# insect-robot.net
KiCad netlist of a schematic drawn in EAGLE
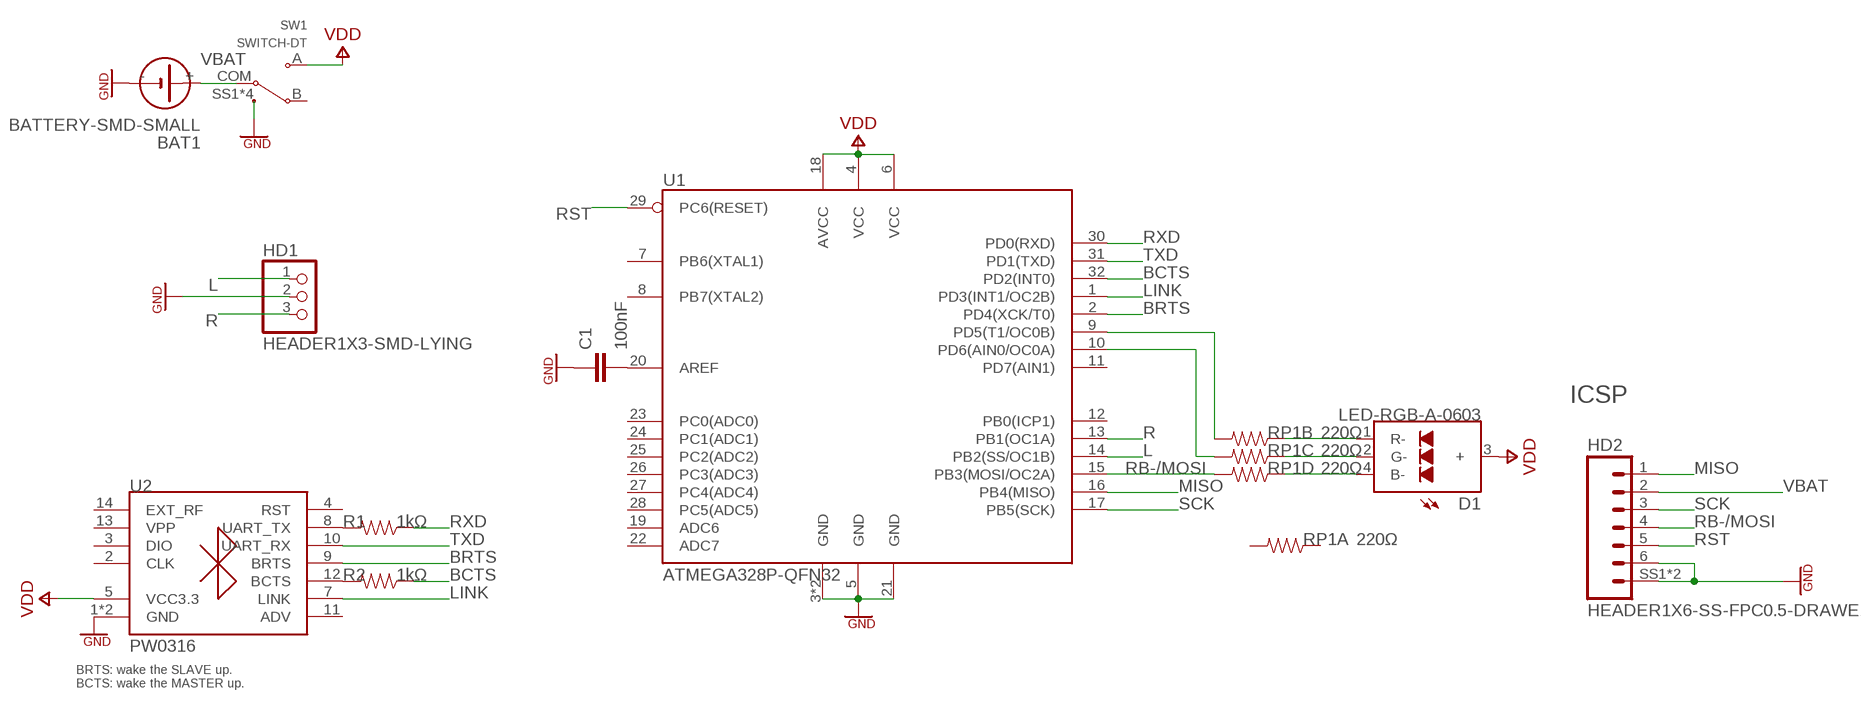
[diagram p0: schematic, sheet 1]

(export (version "E")
  (design (tool "Eeschema 10.0.6"))
  (components
    (comp (ref "BAT1")
      (value "BATTERY-SMD-SMALL")
      (footprint "eagle-import:BAT-SMD-SMALL")
      (libsource (lib "eagle-import") (part "BATTERY-SMD-SMALL"))
    )
    (comp (ref "C1")
      (value "100nF")
      (footprint "eagle-import:SMD0603")
      (libsource (lib "eagle-import") (part "CAP-0603"))
    )
    (comp (ref "D1")
      (value "LED-RGB-A-0603")
      (footprint "eagle-import:LED-0603X2")
      (libsource (lib "eagle-import") (part "LED-RGB-A-0603"))
    )
    (comp (ref "HD1")
      (value "HEADER1X3-SMD-LYING")
      (footprint "eagle-import:SMD-1X3-LYING")
      (libsource (lib "eagle-import") (part "HEADER1X3-SMD-LYING"))
    )
    (comp (ref "HD2")
      (value "HEADER1X6-SS-FPC0.5-DRAWER")
      (footprint "eagle-import:FPC0.5-6-DRAWER")
      (libsource (lib "eagle-import") (part "HEADER1X6-SS-FPC0.5-DRAWER"))
    )
    (comp (ref "R1")
      (value "1kΩ")
      (footprint "eagle-import:SMD0603")
      (libsource (lib "eagle-import") (part "RES-0603"))
    )
    (comp (ref "R2")
      (value "1kΩ")
      (footprint "eagle-import:SMD0603")
      (libsource (lib "eagle-import") (part "RES-0603"))
    )
    (comp (ref "RP1")
      (value "220Ω")
      (footprint "eagle-import:RP0603")
      (libsource (lib "eagle-import") (part "RP-0603"))
    )
    (comp (ref "SW1")
      (value "SWITCH-DT")
      (footprint "eagle-import:SWITCH-SMD-6.7X2.7")
      (libsource (lib "eagle-import") (part "SWITCH-DT"))
    )
    (comp (ref "U1")
      (value "ATMEGA328P-QFN32")
      (footprint "eagle-import:QFN32")
      (libsource (lib "eagle-import") (part "ATMEGA328P-QFN32"))
    )
    (comp (ref "U2")
      (value "PW0316")
      (footprint "eagle-import:PW0316")
      (libsource (lib "eagle-import") (part "PW0316"))
    )
  )
  (nets
    (net (code "1") (name "/BCTS") (class "Default")
      (node (ref "R2") (pin "1") (pinfunction "1_1") (pintype "passive"))
      (node (ref "U1") (pin "32") (pinfunction "PD2(INT0)_32") (pintype "bidirectional"))
    )
    (net (code "2") (name "/BRTS") (class "Default")
      (node (ref "U1") (pin "2") (pinfunction "PD4(XCK/T0)_2") (pintype "bidirectional"))
      (node (ref "U2") (pin "9") (pinfunction "BRTS_9") (pintype "bidirectional"))
    )
    (net (code "3") (name "/L") (class "Default")
      (node (ref "HD1") (pin "1") (pinfunction "1_1") (pintype "passive"))
      (node (ref "U1") (pin "14") (pinfunction "PB2(SS/OC1B)_14") (pintype "bidirectional"))
    )
    (net (code "4") (name "/LINK") (class "Default")
      (node (ref "U1") (pin "1") (pinfunction "PD3(INT1/OC2B)_1") (pintype "bidirectional"))
      (node (ref "U2") (pin "7") (pinfunction "LINK_7") (pintype "bidirectional"))
    )
    (net (code "5") (name "/MISO") (class "Default")
      (node (ref "HD2") (pin "1") (pinfunction "1_1") (pintype "passive"))
      (node (ref "U1") (pin "16") (pinfunction "PB4(MISO)_16") (pintype "bidirectional"))
    )
    (net (code "6") (name "/R") (class "Default")
      (node (ref "HD1") (pin "3") (pinfunction "3_3") (pintype "passive"))
      (node (ref "U1") (pin "13") (pinfunction "PB1(OC1A)_13") (pintype "bidirectional"))
    )
    (net (code "7") (name "/RB-{slash}MOSI") (class "Default")
      (node (ref "HD2") (pin "4") (pinfunction "4_4") (pintype "passive"))
      (node (ref "RP1") (pin "8") (pinfunction "2_8") (pintype "passive"))
      (node (ref "U1") (pin "15") (pinfunction "PB3(MOSI/OC2A)_15") (pintype "bidirectional"))
    )
    (net (code "8") (name "/RST") (class "Default")
      (node (ref "HD2") (pin "5") (pinfunction "5_5") (pintype "passive"))
      (node (ref "U1") (pin "29") (pinfunction "PC6(RESET)_29") (pintype "bidirectional"))
    )
    (net (code "9") (name "/RXD") (class "Default")
      (node (ref "R1") (pin "1") (pinfunction "1_1") (pintype "passive"))
      (node (ref "U1") (pin "30") (pinfunction "PD0(RXD)_30") (pintype "bidirectional"))
    )
    (net (code "10") (name "/SCK") (class "Default")
      (node (ref "HD2") (pin "3") (pinfunction "3_3") (pintype "passive"))
      (node (ref "U1") (pin "17") (pinfunction "PB5(SCK)_17") (pintype "bidirectional"))
    )
    (net (code "11") (name "/TXD") (class "Default")
      (node (ref "U1") (pin "31") (pinfunction "PD1(TXD)_31") (pintype "bidirectional"))
      (node (ref "U2") (pin "10") (pinfunction "UART_RX_10") (pintype "bidirectional"))
    )
    (net (code "12") (name "/VBAT") (class "Default")
      (node (ref "BAT1") (pin "+") (pinfunction "+_+") (pintype "passive"))
      (node (ref "HD2") (pin "2") (pinfunction "2_2") (pintype "passive"))
      (node (ref "SW1") (pin "COM") (pinfunction "COM_COM") (pintype "passive"))
    )
    (net (code "13") (name "GND") (class "Default")
      (node (ref "BAT1") (pin "-") (pinfunction "-_-") (pintype "passive"))
      (node (ref "C1") (pin "1") (pinfunction "1_1") (pintype "passive"))
      (node (ref "HD1") (pin "2") (pinfunction "2_2") (pintype "passive"))
      (node (ref "HD2") (pin "6") (pinfunction "6_6") (pintype "passive"))
      (node (ref "HD2") (pin "SS1") (pinfunction "7_SS1") (pintype "passive"))
      (node (ref "HD2") (pin "SS2") (pinfunction "7_SS2") (pintype "passive"))
      (node (ref "SW1") (pin "SS1") (pinfunction "SS_SS1") (pintype "bidirectional"))
      (node (ref "SW1") (pin "SS2") (pinfunction "SS_SS2") (pintype "bidirectional"))
      (node (ref "SW1") (pin "SS3") (pinfunction "SS_SS3") (pintype "bidirectional"))
      (node (ref "SW1") (pin "SS4") (pinfunction "SS_SS4") (pintype "bidirectional"))
      (node (ref "U1") (pin "21") (pinfunction "GND_21") (pintype "bidirectional"))
      (node (ref "U1") (pin "3") (pinfunction "GND_3") (pintype "bidirectional"))
      (node (ref "U1") (pin "5") (pinfunction "GND_5") (pintype "bidirectional"))
      (node (ref "U1") (pin "EP") (pinfunction "GND_EP") (pintype "bidirectional"))
      (node (ref "U2") (pin "1") (pinfunction "GND_1") (pintype "bidirectional"))
      (node (ref "U2") (pin "6") (pinfunction "GND_6") (pintype "bidirectional"))
    )
    (net (code "14") (name "Net-(D1-B-)") (class "Default")
      (node (ref "D1") (pin "4") (pinfunction "B-_4") (pintype "bidirectional"))
      (node (ref "RP1") (pin "7") (pinfunction "1_7") (pintype "passive"))
    )
    (net (code "15") (name "Net-(D1-G-)") (class "Default")
      (node (ref "D1") (pin "2") (pinfunction "G-_2") (pintype "bidirectional"))
      (node (ref "RP1") (pin "5") (pinfunction "1_5") (pintype "passive"))
    )
    (net (code "16") (name "Net-(D1-R-)") (class "Default")
      (node (ref "D1") (pin "1") (pinfunction "R-_1") (pintype "bidirectional"))
      (node (ref "RP1") (pin "3") (pinfunction "1_3") (pintype "passive"))
    )
    (net (code "17") (name "Net-(RP1B-2)") (class "Default")
      (node (ref "RP1") (pin "4") (pinfunction "2_4") (pintype "passive"))
      (node (ref "U1") (pin "9") (pinfunction "PD5(T1/OC0B)_9") (pintype "bidirectional"))
    )
    (net (code "18") (name "Net-(RP1C-2)") (class "Default")
      (node (ref "RP1") (pin "6") (pinfunction "2_6") (pintype "passive"))
      (node (ref "U1") (pin "10") (pinfunction "PD6(AIN0/OC0A)_10") (pintype "bidirectional"))
    )
    (net (code "19") (name "Net-(U1-AREF)") (class "Default")
      (node (ref "C1") (pin "2") (pinfunction "2_2") (pintype "passive"))
      (node (ref "U1") (pin "20") (pinfunction "AREF_20") (pintype "bidirectional"))
    )
    (net (code "20") (name "Net-(U2-BCTS)") (class "Default")
      (node (ref "R2") (pin "2") (pinfunction "2_2") (pintype "passive"))
      (node (ref "U2") (pin "12") (pinfunction "BCTS_12") (pintype "bidirectional"))
    )
    (net (code "21") (name "Net-(U2-UART_TX)") (class "Default")
      (node (ref "R1") (pin "2") (pinfunction "2_2") (pintype "passive"))
      (node (ref "U2") (pin "8") (pinfunction "UART_TX_8") (pintype "bidirectional"))
    )
    (net (code "22") (name "VDD") (class "Default")
      (node (ref "D1") (pin "3") (pinfunction "+_3") (pintype "bidirectional"))
      (node (ref "SW1") (pin "A") (pinfunction "A_A") (pintype "passive"))
      (node (ref "U1") (pin "18") (pinfunction "AVCC_18") (pintype "bidirectional"))
      (node (ref "U1") (pin "4") (pinfunction "VCC_4") (pintype "bidirectional"))
      (node (ref "U1") (pin "6") (pinfunction "VCC_6") (pintype "bidirectional"))
      (node (ref "U2") (pin "5") (pinfunction "VCC3.3_5") (pintype "bidirectional"))
    )
    (net (code "23") (name "unconnected-(RP1-Pad1)") (class "Default")
      (node (ref "RP1") (pin "1") (pinfunction "1_1") (pintype "passive"))
    )
    (net (code "24") (name "unconnected-(RP1-Pad2)") (class "Default")
      (node (ref "RP1") (pin "2") (pinfunction "2_2") (pintype "passive"))
    )
    (net (code "25") (name "unconnected-(SW1-PadB)") (class "Default")
      (node (ref "SW1") (pin "B") (pinfunction "B_B") (pintype "passive"))
    )
    (net (code "26") (name "unconnected-(U1-ADC6-Pad19)") (class "Default")
      (node (ref "U1") (pin "19") (pinfunction "ADC6_19") (pintype "bidirectional"))
    )
    (net (code "27") (name "unconnected-(U1-ADC7-Pad22)") (class "Default")
      (node (ref "U1") (pin "22") (pinfunction "ADC7_22") (pintype "bidirectional"))
    )
    (net (code "28") (name "unconnected-(U1-PB0(ICP1)-Pad12)") (class "Default")
      (node (ref "U1") (pin "12") (pinfunction "PB0(ICP1)_12") (pintype "bidirectional"))
    )
    (net (code "29") (name "unconnected-(U1-PB6(XTAL1)-Pad7)") (class "Default")
      (node (ref "U1") (pin "7") (pinfunction "PB6(XTAL1)_7") (pintype "bidirectional"))
    )
    (net (code "30") (name "unconnected-(U1-PB7(XTAL2)-Pad8)") (class "Default")
      (node (ref "U1") (pin "8") (pinfunction "PB7(XTAL2)_8") (pintype "bidirectional"))
    )
    (net (code "31") (name "unconnected-(U1-PC0(ADC0)-Pad23)") (class "Default")
      (node (ref "U1") (pin "23") (pinfunction "PC0(ADC0)_23") (pintype "bidirectional"))
    )
    (net (code "32") (name "unconnected-(U1-PC1(ADC1)-Pad24)") (class "Default")
      (node (ref "U1") (pin "24") (pinfunction "PC1(ADC1)_24") (pintype "bidirectional"))
    )
    (net (code "33") (name "unconnected-(U1-PC2(ADC2)-Pad25)") (class "Default")
      (node (ref "U1") (pin "25") (pinfunction "PC2(ADC2)_25") (pintype "bidirectional"))
    )
    (net (code "34") (name "unconnected-(U1-PC3(ADC3)-Pad26)") (class "Default")
      (node (ref "U1") (pin "26") (pinfunction "PC3(ADC3)_26") (pintype "bidirectional"))
    )
    (net (code "35") (name "unconnected-(U1-PC4(ADC4)-Pad27)") (class "Default")
      (node (ref "U1") (pin "27") (pinfunction "PC4(ADC4)_27") (pintype "bidirectional"))
    )
    (net (code "36") (name "unconnected-(U1-PC5(ADC5)-Pad28)") (class "Default")
      (node (ref "U1") (pin "28") (pinfunction "PC5(ADC5)_28") (pintype "bidirectional"))
    )
    (net (code "37") (name "unconnected-(U1-PD7(AIN1)-Pad11)") (class "Default")
      (node (ref "U1") (pin "11") (pinfunction "PD7(AIN1)_11") (pintype "bidirectional"))
    )
    (net (code "38") (name "unconnected-(U2-ADV-Pad11)") (class "Default")
      (node (ref "U2") (pin "11") (pinfunction "ADV_11") (pintype "bidirectional"))
    )
    (net (code "39") (name "unconnected-(U2-CLK-Pad2)") (class "Default")
      (node (ref "U2") (pin "2") (pinfunction "CLK_2") (pintype "bidirectional"))
    )
    (net (code "40") (name "unconnected-(U2-DIO-Pad3)") (class "Default")
      (node (ref "U2") (pin "3") (pinfunction "DIO_3") (pintype "bidirectional"))
    )
    (net (code "41") (name "unconnected-(U2-EXT_RF-Pad14)") (class "Default")
      (node (ref "U2") (pin "14") (pinfunction "EXT_RF_14") (pintype "bidirectional"))
    )
    (net (code "42") (name "unconnected-(U2-RST-Pad4)") (class "Default")
      (node (ref "U2") (pin "4") (pinfunction "RST_4") (pintype "bidirectional"))
    )
    (net (code "43") (name "unconnected-(U2-VPP-Pad13)") (class "Default")
      (node (ref "U2") (pin "13") (pinfunction "VPP_13") (pintype "bidirectional"))
    )
  )
)
